# cryptojawn.net
KiCad netlist of a schematic drawn in EAGLE
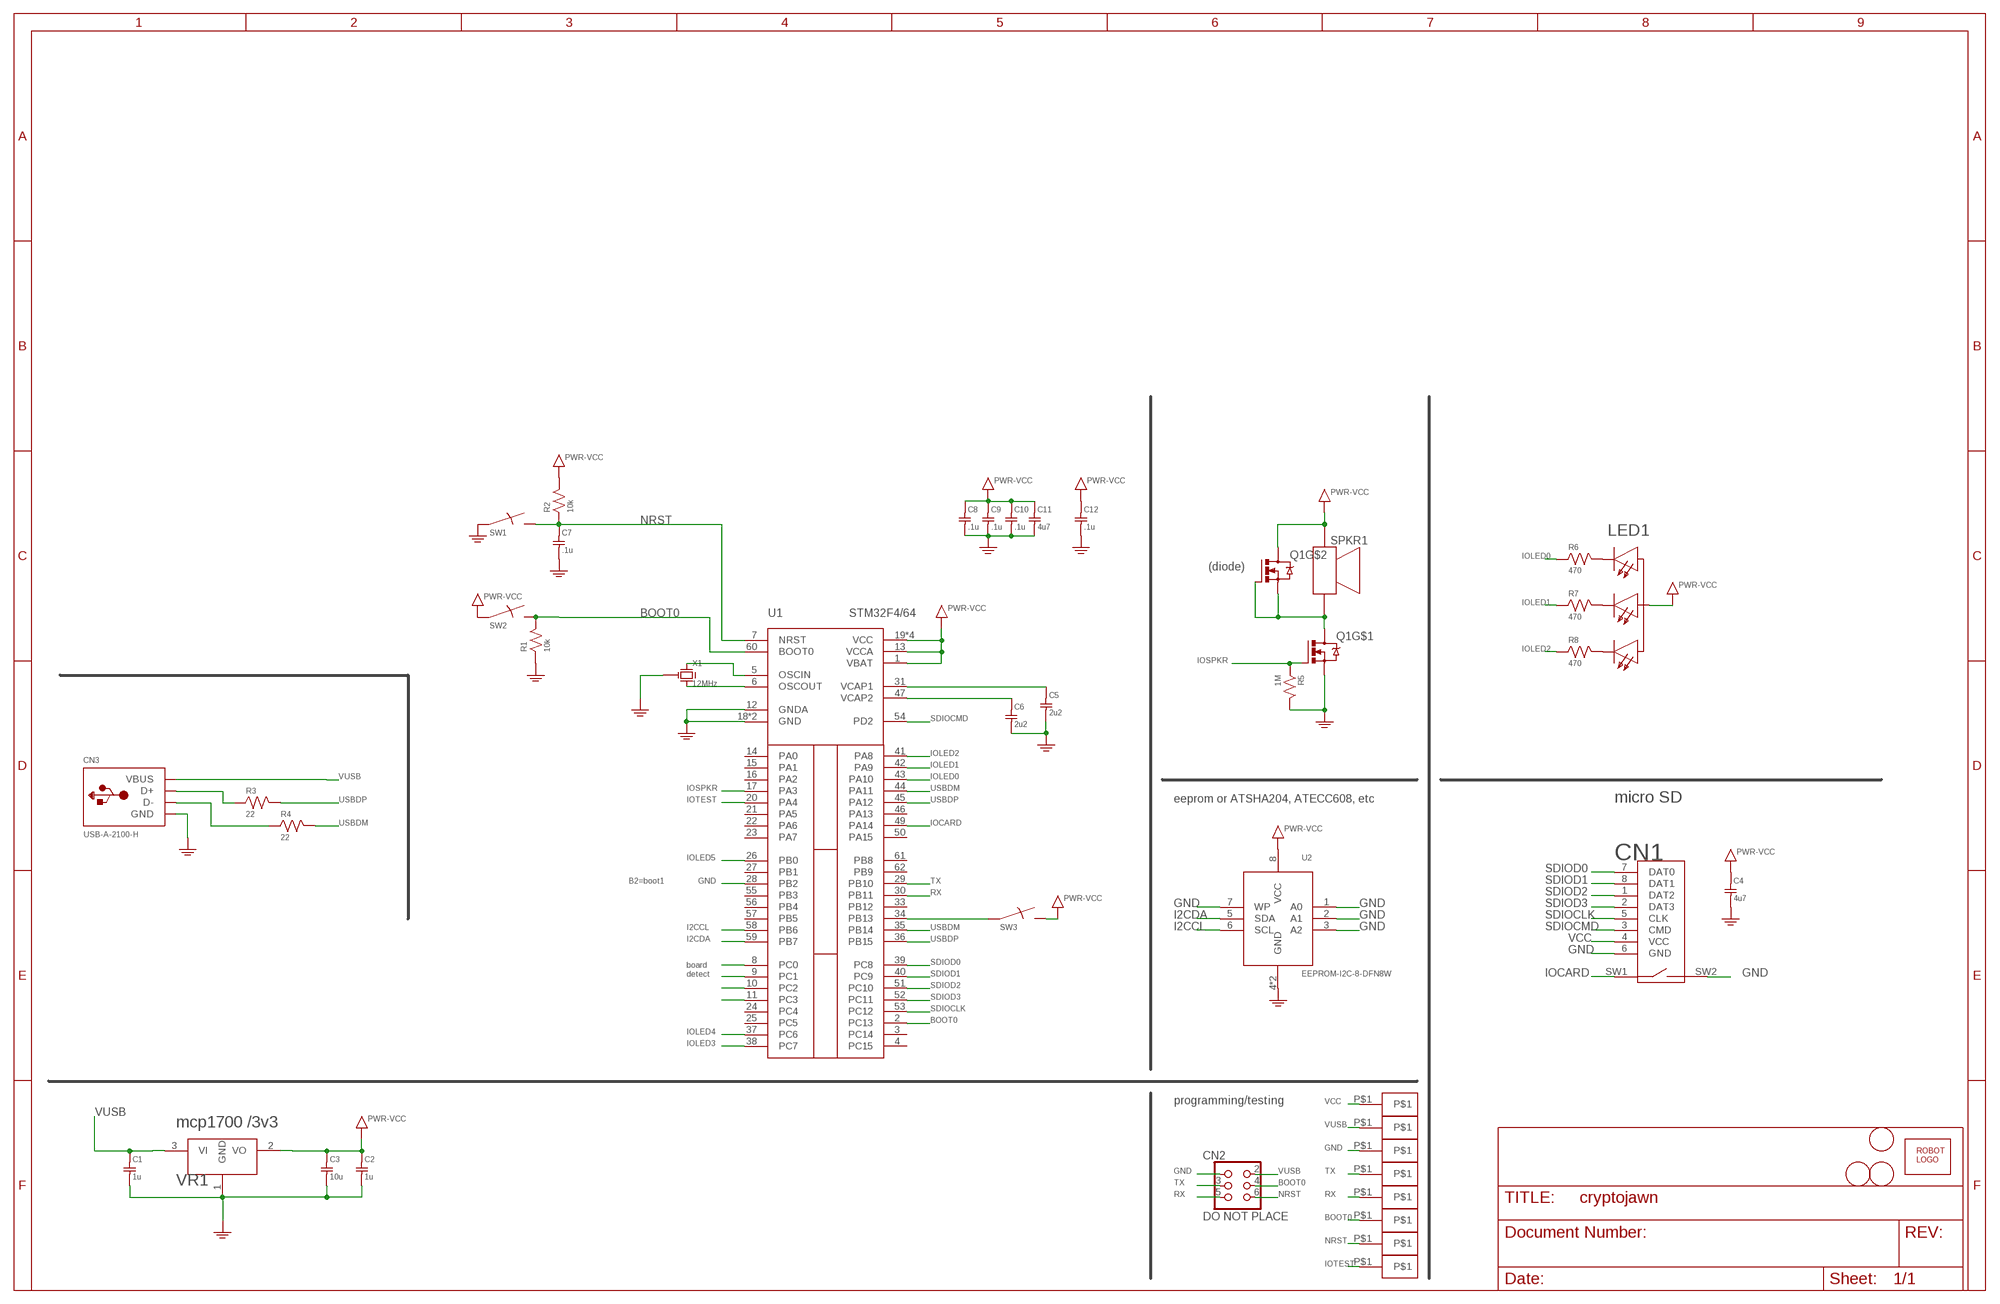
[diagram p0: schematic, sheet 1]

(export (version "E")
  (design (tool "Eeschema 10.0.6"))
  (components
    (comp (ref "C1")
      (value "1u")
      (footprint "eagle-import:SMD0603")
      (libsource (lib "eagle-import") (part "C0603"))
    )
    (comp (ref "C2")
      (value "1u")
      (footprint "eagle-import:SMD0603")
      (libsource (lib "eagle-import") (part "C0603"))
    )
    (comp (ref "C3")
      (value "10u")
      (footprint "eagle-import:SMD0603")
      (libsource (lib "eagle-import") (part "C0603"))
    )
    (comp (ref "C4")
      (value "4u7")
      (footprint "eagle-import:SMD0603")
      (libsource (lib "eagle-import") (part "C0603"))
    )
    (comp (ref "C5")
      (value "2u2")
      (footprint "eagle-import:SMD0603")
      (libsource (lib "eagle-import") (part "C0603"))
    )
    (comp (ref "C6")
      (value "2u2")
      (footprint "eagle-import:SMD0603")
      (libsource (lib "eagle-import") (part "C0603"))
    )
    (comp (ref "C7")
      (value ".1u")
      (footprint "eagle-import:SMD0603")
      (libsource (lib "eagle-import") (part "C0603"))
    )
    (comp (ref "C8")
      (value ".1u")
      (footprint "eagle-import:SMD0603")
      (libsource (lib "eagle-import") (part "C0603"))
    )
    (comp (ref "C9")
      (value ".1u")
      (footprint "eagle-import:SMD0603")
      (libsource (lib "eagle-import") (part "C0603"))
    )
    (comp (ref "C10")
      (value ".1u")
      (footprint "eagle-import:SMD0603")
      (libsource (lib "eagle-import") (part "C0603"))
    )
    (comp (ref "C11")
      (value "4u7")
      (footprint "eagle-import:SMD0603")
      (libsource (lib "eagle-import") (part "C0603"))
    )
    (comp (ref "C12")
      (value ".1u")
      (footprint "eagle-import:SMD0603")
      (libsource (lib "eagle-import") (part "C0603"))
    )
    (comp (ref "CN1")
      (value "MICROSDPLAIN")
      (footprint "eagle-import:MICROSD_MOLEX_FRONT_PLAIN")
      (libsource (lib "eagle-import") (part "MICROSDPLAIN"))
    )
    (comp (ref "CN2")
      (value "DO NOT PLACE")
      (footprint "eagle-import:HEADER-3X2-PTH1.27")
      (libsource (lib "eagle-import") (part "HEADER-3X2-PTH1.27"))
    )
    (comp (ref "CN3")
      (value "USB-A-2100-H")
      (footprint "eagle-import:MOLEX_480372100-HOLE")
      (libsource (lib "eagle-import") (part "USB-A-2100-H"))
    )
    (comp (ref "CN4")
      (value "HEADER-1X1-SPOT")
      (footprint "eagle-import:SPOT")
      (libsource (lib "eagle-import") (part "HEADER-1X1-SPOT"))
    )
    (comp (ref "CN5")
      (value "HEADER-1X1-SPOT")
      (footprint "eagle-import:SPOT")
      (libsource (lib "eagle-import") (part "HEADER-1X1-SPOT"))
    )
    (comp (ref "CN6")
      (value "HEADER-1X1-SPOT")
      (footprint "eagle-import:SPOT")
      (libsource (lib "eagle-import") (part "HEADER-1X1-SPOT"))
    )
    (comp (ref "CN7")
      (value "HEADER-1X1-SPOT")
      (footprint "eagle-import:SPOT")
      (libsource (lib "eagle-import") (part "HEADER-1X1-SPOT"))
    )
    (comp (ref "CN8")
      (value "HEADER-1X1-SPOT")
      (footprint "eagle-import:SPOT")
      (libsource (lib "eagle-import") (part "HEADER-1X1-SPOT"))
    )
    (comp (ref "CN9")
      (value "HEADER-1X1-SPOT")
      (footprint "eagle-import:SPOT")
      (libsource (lib "eagle-import") (part "HEADER-1X1-SPOT"))
    )
    (comp (ref "CN10")
      (value "HEADER-1X1-SPOT")
      (footprint "eagle-import:SPOT")
      (libsource (lib "eagle-import") (part "HEADER-1X1-SPOT"))
    )
    (comp (ref "CN11")
      (value "HEADER-1X1-SPOT")
      (footprint "eagle-import:SPOT")
      (libsource (lib "eagle-import") (part "HEADER-1X1-SPOT"))
    )
    (comp (ref "LED1")
      (value "LED-RGB-CA-PLCC4")
      (footprint "eagle-import:PLCC4-3228")
      (libsource (lib "eagle-import") (part "LED-RGB-CA-PLCC4"))
    )
    (comp (ref "Q1")
      (value "DMN63D8LDW")
      (footprint "eagle-import:SC-70-6")
      (libsource (lib "eagle-import") (part "MOSFET-2N"))
    )
    (comp (ref "R1")
      (value "10k")
      (footprint "eagle-import:SMD0603")
      (libsource (lib "eagle-import") (part "R0603"))
    )
    (comp (ref "R2")
      (value "10k")
      (footprint "eagle-import:SMD0603")
      (libsource (lib "eagle-import") (part "R0603"))
    )
    (comp (ref "R3")
      (value "22")
      (footprint "eagle-import:SMD0603")
      (libsource (lib "eagle-import") (part "R0603"))
    )
    (comp (ref "R4")
      (value "22")
      (footprint "eagle-import:SMD0603")
      (libsource (lib "eagle-import") (part "R0603"))
    )
    (comp (ref "R5")
      (value "1M")
      (footprint "eagle-import:SMD0603")
      (libsource (lib "eagle-import") (part "R0603"))
    )
    (comp (ref "R6")
      (value "470")
      (footprint "eagle-import:SMD0603")
      (libsource (lib "eagle-import") (part "R0603"))
    )
    (comp (ref "R7")
      (value "470")
      (footprint "eagle-import:SMD0603")
      (libsource (lib "eagle-import") (part "R0603"))
    )
    (comp (ref "R8")
      (value "470")
      (footprint "eagle-import:SMD0603")
      (libsource (lib "eagle-import") (part "R0603"))
    )
    (comp (ref "SPKR1")
      (value "SPKR-PUI-0440")
      (footprint "eagle-import:PUI-0440")
      (libsource (lib "eagle-import") (part "SPKR-PUI-0440"))
    )
    (comp (ref "SW1")
      (value "SWITCH-PTS810")
      (footprint "eagle-import:PTS810")
      (libsource (lib "eagle-import") (part "SWITCH-PTS810"))
    )
    (comp (ref "SW2")
      (value "SWITCH-PTS810")
      (footprint "eagle-import:PTS810")
      (libsource (lib "eagle-import") (part "SWITCH-PTS810"))
    )
    (comp (ref "SW3")
      (value "SWITCH-PTS810")
      (footprint "eagle-import:PTS810")
      (libsource (lib "eagle-import") (part "SWITCH-PTS810"))
    )
    (comp (ref "U$1")
      (value "ROBOTMAN-LOGO")
      (footprint "eagle-import:ROBOTMAN-LOGO")
      (libsource (lib "eagle-import") (part "ROBOTMAN-LOGO"))
    )
    (comp (ref "U$2")
      (value "FIDUCIAL")
      (footprint "eagle-import:FIDUCIAL_1MM")
      (libsource (lib "eagle-import") (part "FIDUCIAL"))
    )
    (comp (ref "U$3")
      (value "FIDUCIAL")
      (footprint "eagle-import:FIDUCIAL_1MM")
      (libsource (lib "eagle-import") (part "FIDUCIAL"))
    )
    (comp (ref "U$4")
      (value "FIDUCIAL")
      (footprint "eagle-import:FIDUCIAL_1MM")
      (libsource (lib "eagle-import") (part "FIDUCIAL"))
    )
    (comp (ref "U1")
      (value "STM32F4/64")
      (footprint "eagle-import:TQFP64")
      (libsource (lib "eagle-import") (part "STM32F4/64"))
    )
    (comp (ref "U2")
      (value "EEPROM-I2C-8-DFN8W")
      (footprint "eagle-import:TDFN8EPW")
      (libsource (lib "eagle-import") (part "EEPROM-I2C-8-DFN8W"))
    )
    (comp (ref "VR1")
      (value "mcp1700 /3v3")
      (footprint "eagle-import:SOT-23-3@1")
      (libsource (lib "eagle-import") (part "REGULATOR-SOT23-3"))
    )
    (comp (ref "X1")
      (value "12MHz")
      (footprint "eagle-import:RESONATOR-CSTCE")
      (libsource (lib "eagle-import") (part "RESONATORCTCE"))
    )
  )
  (nets
    (net (code "1") (name "/BOOT0") (class "Default")
      (node (ref "CN2") (pin "4") (pinfunction "P$4_4") (pintype "passive"))
      (node (ref "CN8") (pin "P$1") (pinfunction "P$1_P$1") (pintype "bidirectional"))
      (node (ref "R1") (pin "2") (pinfunction "P$2_2") (pintype "passive"))
      (node (ref "SW2") (pin "P$2") (pinfunction "P$2_P$2") (pintype "passive"))
      (node (ref "SW2") (pin "P$2B") (pinfunction "P$2_P$2B") (pintype "passive"))
      (node (ref "U1") (pin "2") (pinfunction "PC13_2") (pintype "bidirectional"))
      (node (ref "U1") (pin "60") (pinfunction "BOOT0_60") (pintype "bidirectional"))
    )
    (net (code "2") (name "/I2CCL") (class "Default")
      (node (ref "U1") (pin "58") (pinfunction "PB6_58") (pintype "bidirectional"))
      (node (ref "U2") (pin "6") (pinfunction "SCL_6") (pintype "bidirectional"))
    )
    (net (code "3") (name "/I2CDA") (class "Default")
      (node (ref "U1") (pin "59") (pinfunction "PB7_59") (pintype "bidirectional"))
      (node (ref "U2") (pin "5") (pinfunction "SDA_5") (pintype "bidirectional"))
    )
    (net (code "4") (name "/IOCARD") (class "Default")
      (node (ref "CN1") (pin "SW1") (pinfunction "SW1_SW1") (pintype "bidirectional"))
      (node (ref "U1") (pin "49") (pinfunction "PA14_49") (pintype "bidirectional"))
    )
    (net (code "5") (name "/IOLED0") (class "Default")
      (node (ref "R6") (pin "1") (pinfunction "P$1_1") (pintype "passive"))
      (node (ref "U1") (pin "43") (pinfunction "PA10_43") (pintype "bidirectional"))
    )
    (net (code "6") (name "/IOLED1") (class "Default")
      (node (ref "R7") (pin "1") (pinfunction "P$1_1") (pintype "passive"))
      (node (ref "U1") (pin "42") (pinfunction "PA9_42") (pintype "bidirectional"))
    )
    (net (code "7") (name "/IOLED2") (class "Default")
      (node (ref "R8") (pin "1") (pinfunction "P$1_1") (pintype "passive"))
      (node (ref "U1") (pin "41") (pinfunction "PA8_41") (pintype "bidirectional"))
    )
    (net (code "8") (name "/IOLED3") (class "Default")
      (node (ref "U1") (pin "38") (pinfunction "PC7_38") (pintype "bidirectional"))
    )
    (net (code "9") (name "/IOLED4") (class "Default")
      (node (ref "U1") (pin "37") (pinfunction "PC6_37") (pintype "bidirectional"))
    )
    (net (code "10") (name "/IOLED5") (class "Default")
      (node (ref "U1") (pin "26") (pinfunction "PB0_26") (pintype "bidirectional"))
    )
    (net (code "11") (name "/IOSPKR") (class "Default")
      (node (ref "Q1") (pin "2") (pinfunction "G_2") (pintype "passive"))
      (node (ref "R5") (pin "1") (pinfunction "P$1_1") (pintype "passive"))
      (node (ref "U1") (pin "17") (pinfunction "PA3_17") (pintype "bidirectional"))
    )
    (net (code "12") (name "/IOTEST") (class "Default")
      (node (ref "CN11") (pin "P$1") (pinfunction "P$1_P$1") (pintype "bidirectional"))
      (node (ref "U1") (pin "20") (pinfunction "PA4_20") (pintype "bidirectional"))
    )
    (net (code "13") (name "/NRST") (class "Default")
      (node (ref "C7") (pin "1") (pinfunction "P$1_1") (pintype "passive"))
      (node (ref "CN2") (pin "6") (pinfunction "P$6_6") (pintype "passive"))
      (node (ref "CN9") (pin "P$1") (pinfunction "P$1_P$1") (pintype "bidirectional"))
      (node (ref "R2") (pin "1") (pinfunction "P$1_1") (pintype "passive"))
      (node (ref "SW1") (pin "P$2") (pinfunction "P$2_P$2") (pintype "passive"))
      (node (ref "SW1") (pin "P$2B") (pinfunction "P$2_P$2B") (pintype "passive"))
      (node (ref "U1") (pin "7") (pinfunction "NRST_7") (pintype "bidirectional"))
    )
    (net (code "14") (name "/RX") (class "Default")
      (node (ref "CN2") (pin "5") (pinfunction "P$5_5") (pintype "passive"))
      (node (ref "CN7") (pin "P$1") (pinfunction "P$1_P$1") (pintype "bidirectional"))
      (node (ref "U1") (pin "30") (pinfunction "PB11_30") (pintype "bidirectional"))
    )
    (net (code "15") (name "/SDIOCLK") (class "Default")
      (node (ref "CN1") (pin "5") (pinfunction "CLK_5") (pintype "bidirectional"))
      (node (ref "U1") (pin "53") (pinfunction "PC12_53") (pintype "bidirectional"))
    )
    (net (code "16") (name "/SDIOCMD") (class "Default")
      (node (ref "CN1") (pin "3") (pinfunction "CMD_3") (pintype "bidirectional"))
      (node (ref "U1") (pin "54") (pinfunction "PD2_54") (pintype "bidirectional"))
    )
    (net (code "17") (name "/SDIOD0") (class "Default")
      (node (ref "CN1") (pin "7") (pinfunction "DAT0_7") (pintype "bidirectional"))
      (node (ref "U1") (pin "39") (pinfunction "PC8_39") (pintype "bidirectional"))
    )
    (net (code "18") (name "/SDIOD1") (class "Default")
      (node (ref "CN1") (pin "8") (pinfunction "DAT1_8") (pintype "bidirectional"))
      (node (ref "U1") (pin "40") (pinfunction "PC9_40") (pintype "bidirectional"))
    )
    (net (code "19") (name "/SDIOD2") (class "Default")
      (node (ref "CN1") (pin "1") (pinfunction "DAT2_1") (pintype "bidirectional"))
      (node (ref "U1") (pin "51") (pinfunction "PC10_51") (pintype "bidirectional"))
    )
    (net (code "20") (name "/SDIOD3") (class "Default")
      (node (ref "CN1") (pin "2") (pinfunction "DAT3_2") (pintype "bidirectional"))
      (node (ref "U1") (pin "52") (pinfunction "PC11_52") (pintype "bidirectional"))
    )
    (net (code "21") (name "/TX") (class "Default")
      (node (ref "CN2") (pin "3") (pinfunction "P$3_3") (pintype "passive"))
      (node (ref "CN6") (pin "P$1") (pinfunction "P$1_P$1") (pintype "bidirectional"))
      (node (ref "U1") (pin "29") (pinfunction "PB10_29") (pintype "bidirectional"))
    )
    (net (code "22") (name "/USBDM") (class "Default")
      (node (ref "R4") (pin "2") (pinfunction "P$2_2") (pintype "passive"))
      (node (ref "U1") (pin "35") (pinfunction "PB14_35") (pintype "bidirectional"))
      (node (ref "U1") (pin "44") (pinfunction "PA11_44") (pintype "bidirectional"))
    )
    (net (code "23") (name "/USBDP") (class "Default")
      (node (ref "R3") (pin "2") (pinfunction "P$2_2") (pintype "passive"))
      (node (ref "U1") (pin "36") (pinfunction "PB15_36") (pintype "bidirectional"))
      (node (ref "U1") (pin "45") (pinfunction "PA12_45") (pintype "bidirectional"))
    )
    (net (code "24") (name "/VUSB") (class "Default")
      (node (ref "C1") (pin "1") (pinfunction "P$1_1") (pintype "passive"))
      (node (ref "CN2") (pin "2") (pinfunction "P$2_2") (pintype "passive"))
      (node (ref "CN3") (pin "1") (pinfunction "VBUS_1") (pintype "power_in"))
      (node (ref "CN4") (pin "P$1") (pinfunction "P$1_P$1") (pintype "bidirectional"))
      (node (ref "VR1") (pin "3") (pinfunction "VI_3") (pintype "bidirectional"))
    )
    (net (code "25") (name "Net-(C5-P$1)") (class "Default")
      (node (ref "C5") (pin "1") (pinfunction "P$1_1") (pintype "passive"))
      (node (ref "U1") (pin "31") (pinfunction "VCAP1_31") (pintype "bidirectional"))
    )
    (net (code "26") (name "Net-(C6-P$1)") (class "Default")
      (node (ref "C6") (pin "1") (pinfunction "P$1_1") (pintype "passive"))
      (node (ref "U1") (pin "47") (pinfunction "VCAP2_47") (pintype "bidirectional"))
    )
    (net (code "27") (name "Net-(CN3-D+)") (class "Default")
      (node (ref "CN3") (pin "3") (pinfunction "D+_3") (pintype "bidirectional"))
      (node (ref "R3") (pin "1") (pinfunction "P$1_1") (pintype "passive"))
    )
    (net (code "28") (name "Net-(CN3-D-)") (class "Default")
      (node (ref "CN3") (pin "2") (pinfunction "D-_2") (pintype "bidirectional"))
      (node (ref "R4") (pin "1") (pinfunction "P$1_1") (pintype "passive"))
    )
    (net (code "29") (name "Net-(LED1-CB)") (class "Default")
      (node (ref "LED1") (pin "P$4") (pinfunction "CB_P$4") (pintype "passive"))
      (node (ref "R7") (pin "2") (pinfunction "P$2_2") (pintype "passive"))
    )
    (net (code "30") (name "Net-(LED1-CG)") (class "Default")
      (node (ref "LED1") (pin "P$3") (pinfunction "CG_P$3") (pintype "passive"))
      (node (ref "R6") (pin "2") (pinfunction "P$2_2") (pintype "passive"))
    )
    (net (code "31") (name "Net-(LED1-CR)") (class "Default")
      (node (ref "LED1") (pin "P$2") (pinfunction "CR_P$2") (pintype "passive"))
      (node (ref "R8") (pin "2") (pinfunction "P$2_2") (pintype "passive"))
    )
    (net (code "32") (name "Net-(Q1A-D)") (class "Default")
      (node (ref "Q1") (pin "4") (pinfunction "S_4") (pintype "passive"))
      (node (ref "Q1") (pin "5") (pinfunction "G_5") (pintype "passive"))
      (node (ref "Q1") (pin "6") (pinfunction "D_6") (pintype "passive"))
      (node (ref "SPKR1") (pin "P$2") (pinfunction "P2_P$2") (pintype "input"))
    )
    (net (code "33") (name "Net-(U1-OSCIN)") (class "Default")
      (node (ref "U1") (pin "5") (pinfunction "OSCIN_5") (pintype "bidirectional"))
      (node (ref "X1") (pin "1") (pinfunction "X1_1") (pintype "passive"))
    )
    (net (code "34") (name "Net-(U1-OSCOUT)") (class "Default")
      (node (ref "U1") (pin "6") (pinfunction "OSCOUT_6") (pintype "bidirectional"))
      (node (ref "X1") (pin "3") (pinfunction "X2_3") (pintype "passive"))
    )
    (net (code "35") (name "Net-(U1-PB13)") (class "Default")
      (node (ref "SW3") (pin "P$1") (pinfunction "P$1_P$1") (pintype "passive"))
      (node (ref "SW3") (pin "P$1B") (pinfunction "P$1_P$1B") (pintype "passive"))
      (node (ref "U1") (pin "34") (pinfunction "PB13_34") (pintype "bidirectional"))
    )
    (net (code "36") (name "PWR-GND") (class "Default")
      (node (ref "C1") (pin "2") (pinfunction "P$2_2") (pintype "passive"))
      (node (ref "C10") (pin "2") (pinfunction "P$2_2") (pintype "passive"))
      (node (ref "C11") (pin "2") (pinfunction "P$2_2") (pintype "passive"))
      (node (ref "C12") (pin "2") (pinfunction "P$2_2") (pintype "passive"))
      (node (ref "C2") (pin "2") (pinfunction "P$2_2") (pintype "passive"))
      (node (ref "C3") (pin "2") (pinfunction "P$2_2") (pintype "passive"))
      (node (ref "C4") (pin "2") (pinfunction "P$2_2") (pintype "passive"))
      (node (ref "C5") (pin "2") (pinfunction "P$2_2") (pintype "passive"))
      (node (ref "C6") (pin "2") (pinfunction "P$2_2") (pintype "passive"))
      (node (ref "C7") (pin "2") (pinfunction "P$2_2") (pintype "passive"))
      (node (ref "C8") (pin "2") (pinfunction "P$2_2") (pintype "passive"))
      (node (ref "C9") (pin "2") (pinfunction "P$2_2") (pintype "passive"))
      (node (ref "CN1") (pin "6") (pinfunction "GND_6") (pintype "bidirectional"))
      (node (ref "CN1") (pin "SW2") (pinfunction "SW2_SW2") (pintype "bidirectional"))
      (node (ref "CN2") (pin "1") (pinfunction "P$1_1") (pintype "passive"))
      (node (ref "CN3") (pin "4") (pinfunction "GND_4") (pintype "power_in"))
      (node (ref "CN3") (pin "P$1") (pinfunction "GND_P$1") (pintype "power_in"))
      (node (ref "CN3") (pin "P$2") (pinfunction "GND_P$2") (pintype "power_in"))
      (node (ref "CN5") (pin "P$1") (pinfunction "P$1_P$1") (pintype "bidirectional"))
      (node (ref "Q1") (pin "1") (pinfunction "S_1") (pintype "passive"))
      (node (ref "R1") (pin "1") (pinfunction "P$1_1") (pintype "passive"))
      (node (ref "R5") (pin "2") (pinfunction "P$2_2") (pintype "passive"))
      (node (ref "SW1") (pin "P$1") (pinfunction "P$1_P$1") (pintype "passive"))
      (node (ref "SW1") (pin "P$1B") (pinfunction "P$1_P$1B") (pintype "passive"))
      (node (ref "U1") (pin "12") (pinfunction "GNDA_12") (pintype "bidirectional"))
      (node (ref "U1") (pin "18") (pinfunction "GND_18") (pintype "bidirectional"))
      (node (ref "U1") (pin "28") (pinfunction "PB2_28") (pintype "bidirectional"))
      (node (ref "U1") (pin "63") (pinfunction "GND_63") (pintype "bidirectional"))
      (node (ref "U2") (pin "1") (pinfunction "A0_1") (pintype "bidirectional"))
      (node (ref "U2") (pin "2") (pinfunction "A1_2") (pintype "bidirectional"))
      (node (ref "U2") (pin "3") (pinfunction "A2_3") (pintype "bidirectional"))
      (node (ref "U2") (pin "4") (pinfunction "GND_4") (pintype "bidirectional"))
      (node (ref "U2") (pin "7") (pinfunction "WP_7") (pintype "bidirectional"))
      (node (ref "U2") (pin "PAD") (pinfunction "GND_PAD") (pintype "bidirectional"))
      (node (ref "VR1") (pin "1") (pinfunction "GND_1") (pintype "bidirectional"))
      (node (ref "X1") (pin "2") (pinfunction "G_2") (pintype "input"))
    )
    (net (code "37") (name "PWR-VCC") (class "Default")
      (node (ref "C10") (pin "1") (pinfunction "P$1_1") (pintype "passive"))
      (node (ref "C11") (pin "1") (pinfunction "P$1_1") (pintype "passive"))
      (node (ref "C12") (pin "1") (pinfunction "P$1_1") (pintype "passive"))
      (node (ref "C2") (pin "1") (pinfunction "P$1_1") (pintype "passive"))
      (node (ref "C3") (pin "1") (pinfunction "P$1_1") (pintype "passive"))
      (node (ref "C4") (pin "1") (pinfunction "P$1_1") (pintype "passive"))
      (node (ref "C8") (pin "1") (pinfunction "P$1_1") (pintype "passive"))
      (node (ref "C9") (pin "1") (pinfunction "P$1_1") (pintype "passive"))
      (node (ref "CN1") (pin "4") (pinfunction "VCC_4") (pintype "bidirectional"))
      (node (ref "CN10") (pin "P$1") (pinfunction "P$1_P$1") (pintype "bidirectional"))
      (node (ref "LED1") (pin "P$1") (pinfunction "A_P$1") (pintype "passive"))
      (node (ref "Q1") (pin "3") (pinfunction "D_3") (pintype "passive"))
      (node (ref "R2") (pin "2") (pinfunction "P$2_2") (pintype "passive"))
      (node (ref "SPKR1") (pin "P$1") (pinfunction "P1_P$1") (pintype "input"))
      (node (ref "SW2") (pin "P$1") (pinfunction "P$1_P$1") (pintype "passive"))
      (node (ref "SW2") (pin "P$1B") (pinfunction "P$1_P$1B") (pintype "passive"))
      (node (ref "SW3") (pin "P$2") (pinfunction "P$2_P$2") (pintype "passive"))
      (node (ref "SW3") (pin "P$2B") (pinfunction "P$2_P$2B") (pintype "passive"))
      (node (ref "U1") (pin "1") (pinfunction "VBAT_1") (pintype "bidirectional"))
      (node (ref "U1") (pin "13") (pinfunction "VCCA_13") (pintype "bidirectional"))
      (node (ref "U1") (pin "19") (pinfunction "VCC_19") (pintype "bidirectional"))
      (node (ref "U1") (pin "32") (pinfunction "VCC_32") (pintype "bidirectional"))
      (node (ref "U1") (pin "48") (pinfunction "VCC_48") (pintype "bidirectional"))
      (node (ref "U1") (pin "64") (pinfunction "VCC_64") (pintype "bidirectional"))
      (node (ref "U2") (pin "8") (pinfunction "VCC_8") (pintype "bidirectional"))
      (node (ref "VR1") (pin "2") (pinfunction "VO_2") (pintype "bidirectional"))
    )
    (net (code "38") (name "unconnected-(U1-PA0-Pad14)") (class "Default")
      (node (ref "U1") (pin "14") (pinfunction "PA0_14") (pintype "bidirectional"))
    )
    (net (code "39") (name "unconnected-(U1-PA1-Pad15)") (class "Default")
      (node (ref "U1") (pin "15") (pinfunction "PA1_15") (pintype "bidirectional"))
    )
    (net (code "40") (name "unconnected-(U1-PA2-Pad16)") (class "Default")
      (node (ref "U1") (pin "16") (pinfunction "PA2_16") (pintype "bidirectional"))
    )
    (net (code "41") (name "unconnected-(U1-PA5-Pad21)") (class "Default")
      (node (ref "U1") (pin "21") (pinfunction "PA5_21") (pintype "bidirectional"))
    )
    (net (code "42") (name "unconnected-(U1-PA6-Pad22)") (class "Default")
      (node (ref "U1") (pin "22") (pinfunction "PA6_22") (pintype "bidirectional"))
    )
    (net (code "43") (name "unconnected-(U1-PA7-Pad23)") (class "Default")
      (node (ref "U1") (pin "23") (pinfunction "PA7_23") (pintype "bidirectional"))
    )
    (net (code "44") (name "unconnected-(U1-PA13-Pad46)") (class "Default")
      (node (ref "U1") (pin "46") (pinfunction "PA13_46") (pintype "bidirectional"))
    )
    (net (code "45") (name "unconnected-(U1-PA15-Pad50)") (class "Default")
      (node (ref "U1") (pin "50") (pinfunction "PA15_50") (pintype "bidirectional"))
    )
    (net (code "46") (name "unconnected-(U1-PB1-Pad27)") (class "Default")
      (node (ref "U1") (pin "27") (pinfunction "PB1_27") (pintype "bidirectional"))
    )
    (net (code "47") (name "unconnected-(U1-PB3-Pad55)") (class "Default")
      (node (ref "U1") (pin "55") (pinfunction "PB3_55") (pintype "bidirectional"))
    )
    (net (code "48") (name "unconnected-(U1-PB4-Pad56)") (class "Default")
      (node (ref "U1") (pin "56") (pinfunction "PB4_56") (pintype "bidirectional"))
    )
    (net (code "49") (name "unconnected-(U1-PB5-Pad57)") (class "Default")
      (node (ref "U1") (pin "57") (pinfunction "PB5_57") (pintype "bidirectional"))
    )
    (net (code "50") (name "unconnected-(U1-PB8-Pad61)") (class "Default")
      (node (ref "U1") (pin "61") (pinfunction "PB8_61") (pintype "bidirectional"))
    )
    (net (code "51") (name "unconnected-(U1-PB9-Pad62)") (class "Default")
      (node (ref "U1") (pin "62") (pinfunction "PB9_62") (pintype "bidirectional"))
    )
    (net (code "52") (name "unconnected-(U1-PB12-Pad33)") (class "Default")
      (node (ref "U1") (pin "33") (pinfunction "PB12_33") (pintype "bidirectional"))
    )
    (net (code "53") (name "unconnected-(U1-PC0-Pad8)") (class "Default")
      (node (ref "U1") (pin "8") (pinfunction "PC0_8") (pintype "bidirectional"))
    )
    (net (code "54") (name "unconnected-(U1-PC1-Pad9)") (class "Default")
      (node (ref "U1") (pin "9") (pinfunction "PC1_9") (pintype "bidirectional"))
    )
    (net (code "55") (name "unconnected-(U1-PC2-Pad10)") (class "Default")
      (node (ref "U1") (pin "10") (pinfunction "PC2_10") (pintype "bidirectional"))
    )
    (net (code "56") (name "unconnected-(U1-PC3-Pad11)") (class "Default")
      (node (ref "U1") (pin "11") (pinfunction "PC3_11") (pintype "bidirectional"))
    )
    (net (code "57") (name "unconnected-(U1-PC4-Pad24)") (class "Default")
      (node (ref "U1") (pin "24") (pinfunction "PC4_24") (pintype "bidirectional"))
    )
    (net (code "58") (name "unconnected-(U1-PC5-Pad25)") (class "Default")
      (node (ref "U1") (pin "25") (pinfunction "PC5_25") (pintype "bidirectional"))
    )
    (net (code "59") (name "unconnected-(U1-PC14-Pad3)") (class "Default")
      (node (ref "U1") (pin "3") (pinfunction "PC14_3") (pintype "bidirectional"))
    )
    (net (code "60") (name "unconnected-(U1-PC15-Pad4)") (class "Default")
      (node (ref "U1") (pin "4") (pinfunction "PC15_4") (pintype "bidirectional"))
    )
  )
)
